# wireless-dong-mk-2_0.net
KiCad netlist of a schematic drawn in EAGLE
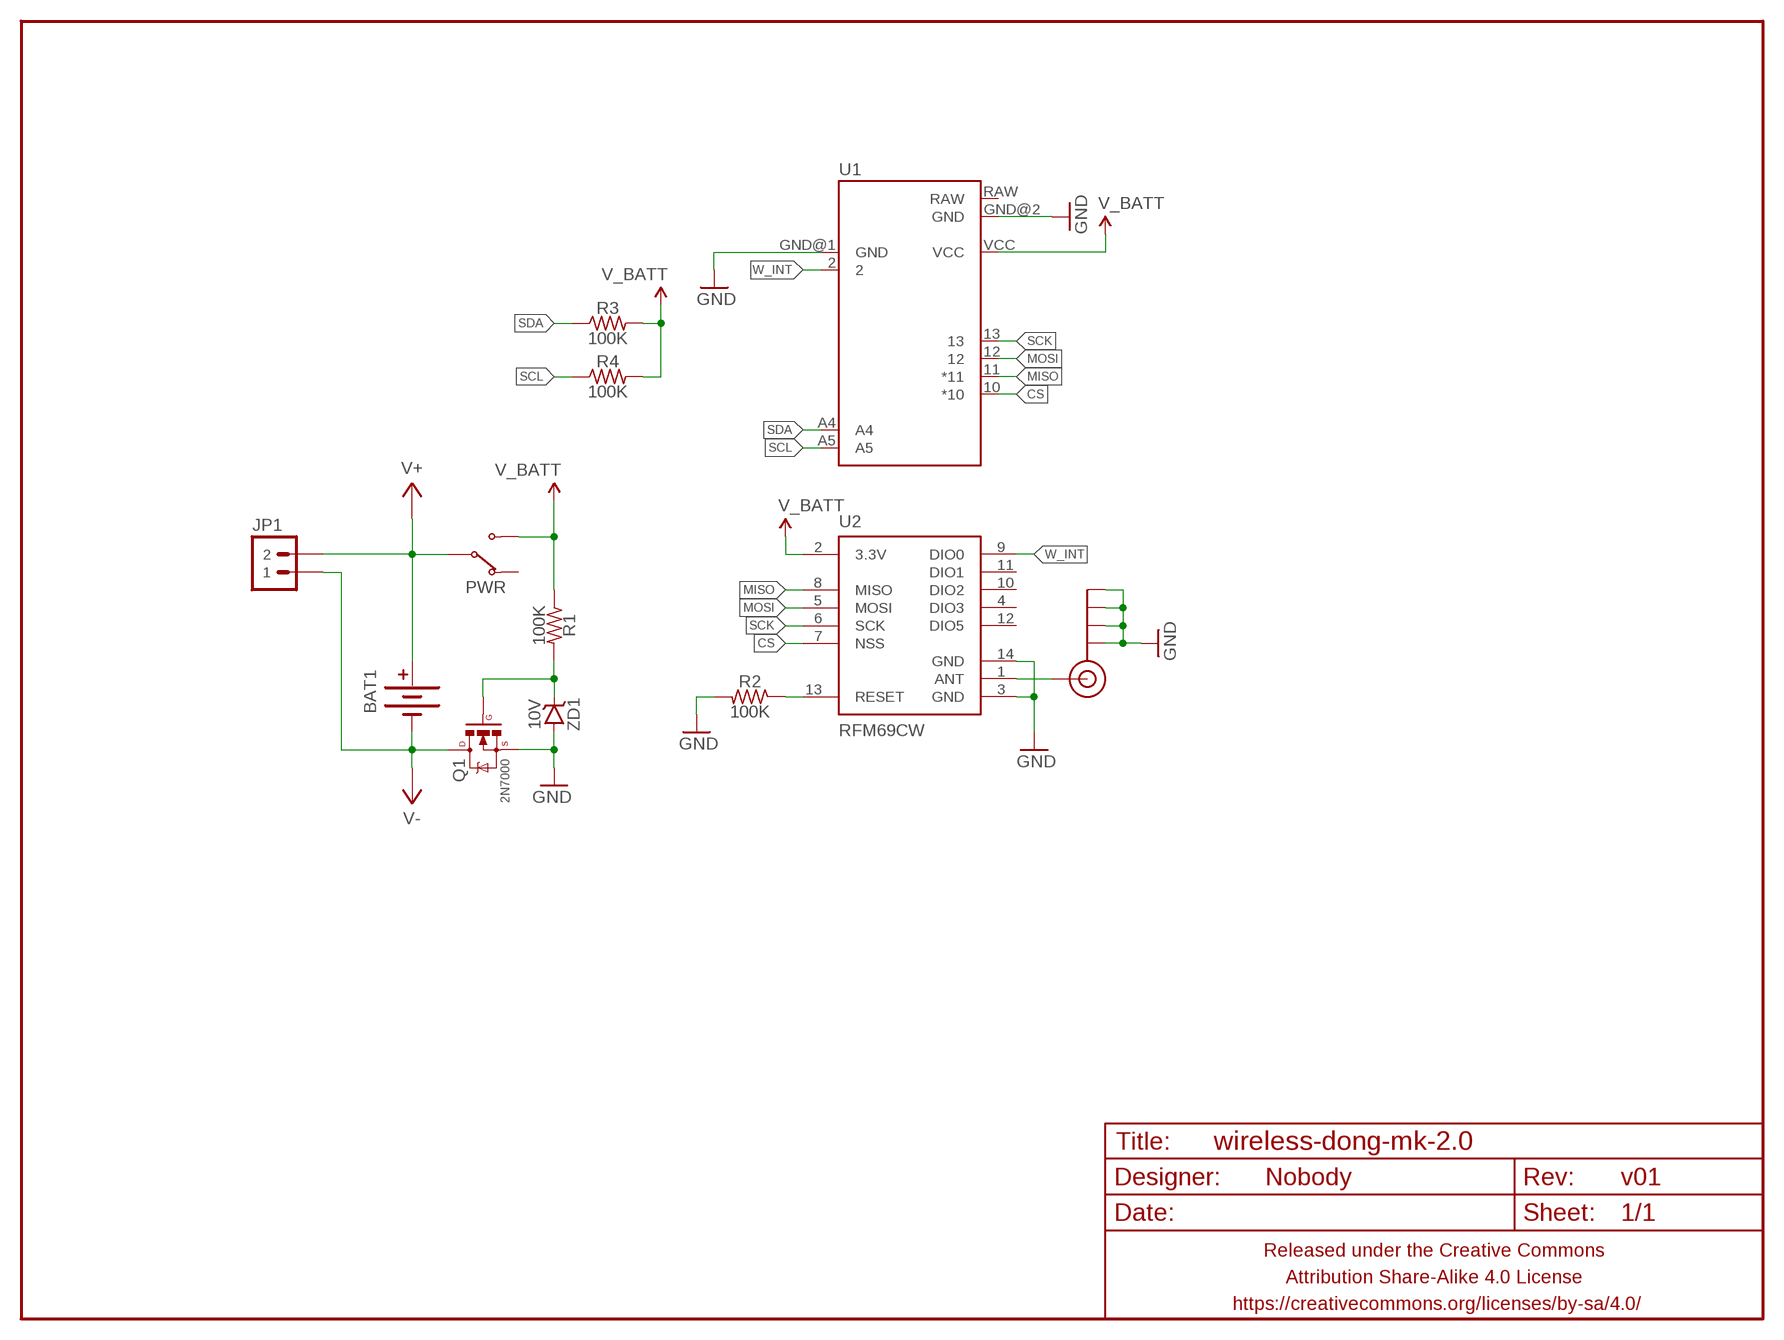
[diagram p0: schematic, sheet 1]

(export (version "E")
  (design (tool "Eeschema 10.0.6"))
  (components
    (comp (ref "BAT1")
      (value "BATTERY20PTH_TOPLOAD")
      (footprint "eagle-import:BATTCON_20MM_PTH_TOPLOAD")
      (libsource (lib "eagle-import") (part "BATTERY20PTH_TOPLOAD"))
    )
    (comp (ref "FRAME1")
      (value "FRAME-LETTERNO_PACKAGE")
      (footprint "eagle-import:DUMMY")
      (fields (field (name "DESIGNER") "Nobody"))
      (libsource (lib "eagle-import") (part "FRAME-LETTERNO_PACKAGE"))
    )
    (comp (ref "J$1")
      (value "SMA_EDGE")
      (footprint "eagle-import:SMA-EDGE")
      (libsource (lib "eagle-import") (part "SMA_EDGE"))
    )
    (comp (ref "JP1")
      (value "M02PTH-CENTERED-R+")
      (footprint "eagle-import:1X02-CENTER-R+")
      (libsource (lib "eagle-import") (part "M02PTH-CENTERED-R+"))
    )
    (comp (ref "PWR")
      (value "SWITCH-SPDTPTH-RA-2.54MM")
      (footprint "eagle-import:SPDT-RA-2.54MM")
      (libsource (lib "eagle-import") (part "SWITCH-SPDTPTH-RA-2.54MM"))
    )
    (comp (ref "Q1")
      (value "2N7000")
      (footprint "eagle-import:SOT23")
      (libsource (lib "eagle-import") (part "MOSFET-NCHANNELIRLML2502"))
    )
    (comp (ref "R1")
      (value "100K")
      (footprint "eagle-import:R0603")
      (libsource (lib "eagle-import") (part "RESISTORR0603"))
    )
    (comp (ref "R2")
      (value "100K")
      (footprint "eagle-import:R0603")
      (libsource (lib "eagle-import") (part "RESISTORR0603"))
    )
    (comp (ref "R3")
      (value "100K")
      (footprint "eagle-import:R0603")
      (libsource (lib "eagle-import") (part "RESISTORR0603"))
    )
    (comp (ref "R4")
      (value "100K")
      (footprint "eagle-import:R0603")
      (libsource (lib "eagle-import") (part "RESISTORR0603"))
    )
    (comp (ref "U1")
      (value "ARDUINO_PRO_MINI_BOATON_ONE_MF")
      (footprint "eagle-import:ARDUINO_PRO_MINI_BOAT")
      (libsource (lib "eagle-import") (part "ARDUINO_PRO_MINI_BOATON_ONE_MF"))
    )
    (comp (ref "U2")
      (value "RFM69CW")
      (footprint "eagle-import:RFM69CW-XXXS2")
      (libsource (lib "eagle-import") (part "RFM69CW"))
    )
    (comp (ref "ZD1")
      (value "10V")
      (footprint "eagle-import:SOT23")
      (libsource (lib "eagle-import") (part "DIODE-ZENERSOT23"))
    )
  )
  (nets
    (net (code "1") (name "CS") (class "Default")
      (node (ref "U1") (pin "10") (pinfunction "*10_10") (pintype "bidirectional"))
      (node (ref "U2") (pin "7") (pinfunction "NSS_7") (pintype "input"))
    )
    (net (code "2") (name "GND") (class "Default")
      (node (ref "J$1") (pin "GND@0") (pinfunction "GND_GND@0") (pintype "bidirectional"))
      (node (ref "J$1") (pin "GND@1") (pinfunction "GND_GND@1") (pintype "bidirectional"))
      (node (ref "J$1") (pin "GND@2") (pinfunction "GND_GND@2") (pintype "bidirectional"))
      (node (ref "J$1") (pin "GND@3") (pinfunction "GND_GND@3") (pintype "bidirectional"))
      (node (ref "Q1") (pin "2") (pinfunction "S_2") (pintype "passive"))
      (node (ref "R2") (pin "2") (pinfunction "2_2") (pintype "passive"))
      (node (ref "U1") (pin "GND@1") (pinfunction "GND_GND@1") (pintype "bidirectional"))
      (node (ref "U1") (pin "GND@2") (pinfunction "GND_GND@2") (pintype "bidirectional"))
      (node (ref "U2") (pin "14") (pinfunction "GND_14") (pintype "power_in"))
      (node (ref "U2") (pin "3") (pinfunction "GND_3") (pintype "power_in"))
      (node (ref "ZD1") (pin "1") (pinfunction "A_1") (pintype "passive"))
      (node (ref "ZD1") (pin "2") (pinfunction "A_2") (pintype "passive"))
    )
    (net (code "3") (name "MISO") (class "Default")
      (node (ref "U1") (pin "11") (pinfunction "*11_11") (pintype "bidirectional"))
      (node (ref "U2") (pin "8") (pinfunction "MISO_8") (pintype "bidirectional"))
    )
    (net (code "4") (name "MOSI") (class "Default")
      (node (ref "U1") (pin "12") (pinfunction "12_12") (pintype "bidirectional"))
      (node (ref "U2") (pin "5") (pinfunction "MOSI_5") (pintype "input"))
    )
    (net (code "5") (name "Net-(J$1-SIGNAL)") (class "Default")
      (node (ref "J$1") (pin "SIG") (pinfunction "SIGNAL_SIG") (pintype "bidirectional"))
      (node (ref "U2") (pin "1") (pinfunction "ANT_1") (pintype "passive"))
    )
    (net (code "6") (name "Net-(Q1-G)") (class "Default")
      (node (ref "Q1") (pin "1") (pinfunction "G_1") (pintype "passive"))
      (node (ref "R1") (pin "2") (pinfunction "2_2") (pintype "passive"))
      (node (ref "ZD1") (pin "3") (pinfunction "C_3") (pintype "passive"))
    )
    (net (code "7") (name "Net-(U2-RESET)") (class "Default")
      (node (ref "R2") (pin "1") (pinfunction "1_1") (pintype "passive"))
      (node (ref "U2") (pin "13") (pinfunction "RESET_13") (pintype "input"))
    )
    (net (code "8") (name "SCK") (class "Default")
      (node (ref "U1") (pin "13") (pinfunction "13_13") (pintype "bidirectional"))
      (node (ref "U2") (pin "6") (pinfunction "SCK_6") (pintype "input"))
    )
    (net (code "9") (name "SCL") (class "Default")
      (node (ref "R4") (pin "1") (pinfunction "1_1") (pintype "passive"))
      (node (ref "U1") (pin "A5") (pinfunction "A5_A5") (pintype "bidirectional"))
    )
    (net (code "10") (name "SDA") (class "Default")
      (node (ref "R3") (pin "1") (pinfunction "1_1") (pintype "passive"))
      (node (ref "U1") (pin "A4") (pinfunction "A4_A4") (pintype "bidirectional"))
    )
    (net (code "11") (name "V+") (class "Default")
      (node (ref "BAT1") (pin "+") (pinfunction "+_+") (pintype "power_in"))
      (node (ref "JP1") (pin "2") (pinfunction "2_2") (pintype "passive"))
      (node (ref "PWR") (pin "2") (pinfunction "COM_2") (pintype "passive"))
    )
    (net (code "12") (name "V-") (class "Default")
      (node (ref "BAT1") (pin "-") (pinfunction "-_-") (pintype "power_in"))
      (node (ref "JP1") (pin "1") (pinfunction "1_1") (pintype "passive"))
      (node (ref "Q1") (pin "3") (pinfunction "D_3") (pintype "passive"))
    )
    (net (code "13") (name "V_BATT") (class "Default")
      (node (ref "PWR") (pin "3") (pinfunction "NO_3") (pintype "passive"))
      (node (ref "R1") (pin "1") (pinfunction "1_1") (pintype "passive"))
      (node (ref "R3") (pin "2") (pinfunction "2_2") (pintype "passive"))
      (node (ref "R4") (pin "2") (pinfunction "2_2") (pintype "passive"))
      (node (ref "U1") (pin "VCC") (pinfunction "VCC_VCC") (pintype "bidirectional"))
      (node (ref "U2") (pin "2") (pinfunction "3.3V_2") (pintype "power_in"))
    )
    (net (code "14") (name "W_INT") (class "Default")
      (node (ref "U1") (pin "2") (pinfunction "2_2") (pintype "bidirectional"))
      (node (ref "U2") (pin "9") (pinfunction "DIO0_9") (pintype "bidirectional"))
    )
    (net (code "15") (name "unconnected-(PWR-NC-Pad1)") (class "Default")
      (node (ref "PWR") (pin "1") (pinfunction "NC_1") (pintype "passive"))
    )
    (net (code "16") (name "unconnected-(U1-PadRAW)") (class "Default")
      (node (ref "U1") (pin "RAW") (pinfunction "RAW_RAW") (pintype "bidirectional"))
    )
    (net (code "17") (name "unconnected-(U2-DIO1-Pad11)") (class "Default")
      (node (ref "U2") (pin "11") (pinfunction "DIO1_11") (pintype "bidirectional"))
    )
    (net (code "18") (name "unconnected-(U2-DIO2-Pad10)") (class "Default")
      (node (ref "U2") (pin "10") (pinfunction "DIO2_10") (pintype "bidirectional"))
    )
    (net (code "19") (name "unconnected-(U2-DIO3-Pad4)") (class "Default")
      (node (ref "U2") (pin "4") (pinfunction "DIO3_4") (pintype "bidirectional"))
    )
    (net (code "20") (name "unconnected-(U2-DIO5-Pad12)") (class "Default")
      (node (ref "U2") (pin "12") (pinfunction "DIO5_12") (pintype "bidirectional"))
    )
  )
)
